# Yun_Shield_Teensy_Adapter.net
KiCad netlist of a schematic drawn in EAGLE
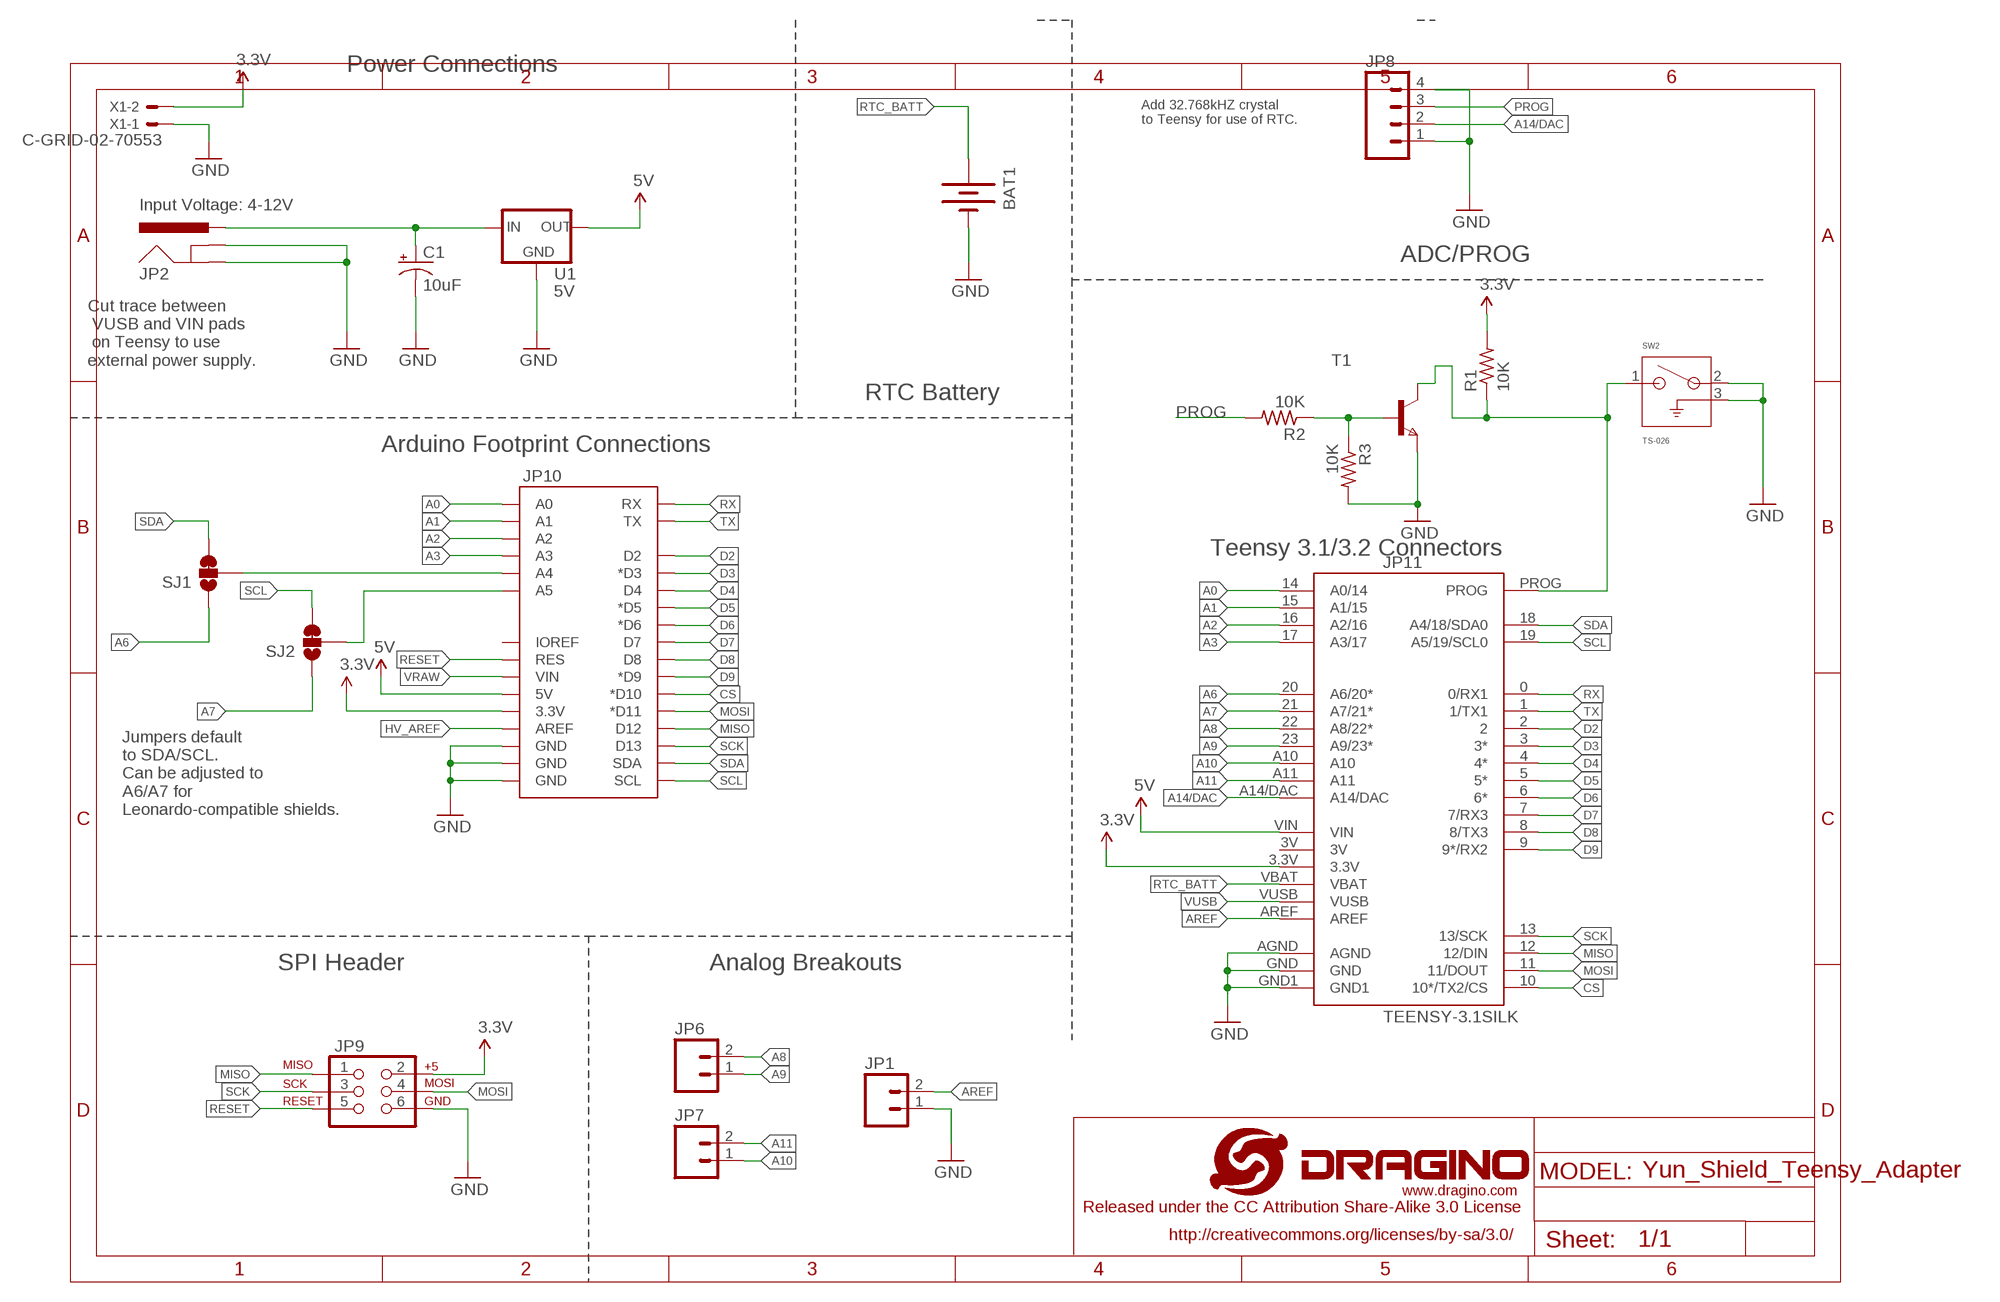
[diagram p0: schematic, sheet 1]

(export (version "E")
  (design (tool "Eeschema 10.0.6"))
  (components
    (comp (ref "BAT1")
      (value "BATTERY12PTH")
      (footprint "eagle-import:BATTCON_12MM_PTH")
      (libsource (lib "eagle-import") (part "BATTERY12PTH"))
    )
    (comp (ref "C1")
      (value "10uF")
      (footprint "eagle-import:CPOL-RADIAL-10UF-25V")
      (libsource (lib "eagle-import") (part "10UF-25V-20%(PTH)"))
    )
    (comp (ref "JP1")
      (value "M02PTH")
      (footprint "eagle-import:1X02")
      (libsource (lib "eagle-import") (part "M02PTH"))
    )
    (comp (ref "JP2")
      (value "POWER_JACKPTH_LOCK")
      (footprint "eagle-import:POWER_JACK_PTH_LOCK")
      (libsource (lib "eagle-import") (part "POWER_JACKPTH_LOCK"))
    )
    (comp (ref "JP6")
      (value "M02PTH")
      (footprint "eagle-import:1X02")
      (libsource (lib "eagle-import") (part "M02PTH"))
    )
    (comp (ref "JP7")
      (value "M02PTH")
      (footprint "eagle-import:1X02")
      (libsource (lib "eagle-import") (part "M02PTH"))
    )
    (comp (ref "JP8")
      (value "M04PTH")
      (footprint "eagle-import:1X04")
      (libsource (lib "eagle-import") (part "M04PTH"))
    )
    (comp (ref "JP9")
      (value "AVR_SPI_PRG_6PTH")
      (footprint "eagle-import:2X3")
      (libsource (lib "eagle-import") (part "AVR_SPI_PRG_6PTH"))
    )
    (comp (ref "JP10")
      (value "ARDUINO_R3_SHIELDUNO_R3_SHIELD_HOLES")
      (footprint "eagle-import:UNO_R3_SHIELD_HOLES")
      (libsource (lib "eagle-import") (part "ARDUINO_R3_SHIELDUNO_R3_SHIELD_HOLES"))
    )
    (comp (ref "JP11")
      (value "TEENSY-3.1SILK")
      (footprint "eagle-import:TEENSY-3.1")
      (libsource (lib "eagle-import") (part "TEENSY-3.1SILK"))
    )
    (comp (ref "R1")
      (value "10K")
      (footprint "eagle-import:0204_5")
      (libsource (lib "eagle-import") (part "R-US_0204/5"))
    )
    (comp (ref "R2")
      (value "10K")
      (footprint "eagle-import:0204_5")
      (libsource (lib "eagle-import") (part "R-US_0204/5"))
    )
    (comp (ref "R3")
      (value "10K")
      (footprint "eagle-import:0204_5")
      (libsource (lib "eagle-import") (part "R-US_0204/5"))
    )
    (comp (ref "SJ1")
      (value "JUMPER-PAD-3-2OF3_NC_BY_TRACE_SMALL")
      (footprint "eagle-import:PAD-JUMPER-3-2OF3_NC_BY_TRACE_YES_SILK_FULL_BOX")
      (libsource (lib "eagle-import") (part "JUMPER-PAD-3-2OF3_NC_BY_TRACE_SMALL"))
    )
    (comp (ref "SJ2")
      (value "JUMPER-PAD-3-2OF3_NC_BY_TRACE_SMALL")
      (footprint "eagle-import:PAD-JUMPER-3-2OF3_NC_BY_TRACE_YES_SILK_FULL_BOX")
      (libsource (lib "eagle-import") (part "JUMPER-PAD-3-2OF3_NC_BY_TRACE_SMALL"))
    )
    (comp (ref "SW2")
      (value "TS-026")
      (footprint "eagle-import:TS-026")
      (libsource (lib "eagle-import") (part "TS-026"))
    )
    (comp (ref "T1")
      (value "NPN-E3L")
      (footprint "eagle-import:E3LINE")
      (libsource (lib "eagle-import") (part "NPN-E3L"))
    )
    (comp (ref "U$1")
      (value "LOGO-NEW")
      (footprint "eagle-import:LOGO-SILK-NEW")
      (libsource (lib "eagle-import") (part "LOGO-NEW"))
    )
    (comp (ref "U1")
      (value "5V")
      (footprint "eagle-import:TO-220-ALT")
      (libsource (lib "eagle-import") (part "V_REG_78XX-TO-220"))
    )
    (comp (ref "X1")
      (value "C-GRID-02-70553")
      (footprint "eagle-import:70553-02")
      (libsource (lib "eagle-import") (part "C-GRID-02-70553"))
    )
  )
  (nets
    (net (code "1") (name "3.3V") (class "Default")
      (node (ref "JP10") (pin "3.3V") (pinfunction "3.3V_3.3V") (pintype "bidirectional"))
      (node (ref "JP11") (pin "3.3V") (pinfunction "3.3V_3.3V") (pintype "bidirectional"))
      (node (ref "JP9") (pin "2") (pinfunction "2_2") (pintype "passive"))
      (node (ref "R1") (pin "2") (pinfunction "2_2") (pintype "passive"))
      (node (ref "X1") (pin "2") (pinfunction "S_2") (pintype "passive"))
    )
    (net (code "2") (name "5V") (class "Default")
      (node (ref "JP10") (pin "5V") (pinfunction "5V_5V") (pintype "bidirectional"))
      (node (ref "JP11") (pin "VIN") (pinfunction "VIN_VIN") (pintype "bidirectional"))
      (node (ref "U1") (pin "OUT") (pinfunction "OUT_OUT") (pintype "output"))
    )
    (net (code "3") (name "A0") (class "Default")
      (node (ref "JP10") (pin "A0") (pinfunction "A0_A0") (pintype "bidirectional"))
      (node (ref "JP11") (pin "14") (pinfunction "A0/14_14") (pintype "bidirectional"))
    )
    (net (code "4") (name "A1") (class "Default")
      (node (ref "JP10") (pin "A1") (pinfunction "A1_A1") (pintype "bidirectional"))
      (node (ref "JP11") (pin "15") (pinfunction "A1/15_15") (pintype "bidirectional"))
    )
    (net (code "5") (name "A2") (class "Default")
      (node (ref "JP10") (pin "A2") (pinfunction "A2_A2") (pintype "bidirectional"))
      (node (ref "JP11") (pin "16") (pinfunction "A2/16_16") (pintype "bidirectional"))
    )
    (net (code "6") (name "A3") (class "Default")
      (node (ref "JP10") (pin "A3") (pinfunction "A3_A3") (pintype "bidirectional"))
      (node (ref "JP11") (pin "17") (pinfunction "A3/17_17") (pintype "bidirectional"))
    )
    (net (code "7") (name "A6") (class "Default")
      (node (ref "JP11") (pin "20") (pinfunction "A6/20*_20") (pintype "bidirectional"))
      (node (ref "SJ1") (pin "1") (pinfunction "1_1") (pintype "passive"))
    )
    (net (code "8") (name "A7") (class "Default")
      (node (ref "JP11") (pin "21") (pinfunction "A7/21*_21") (pintype "bidirectional"))
      (node (ref "SJ2") (pin "1") (pinfunction "1_1") (pintype "passive"))
    )
    (net (code "9") (name "A8") (class "Default")
      (node (ref "JP11") (pin "22") (pinfunction "A8/22*_22") (pintype "bidirectional"))
      (node (ref "JP6") (pin "2") (pinfunction "2_2") (pintype "passive"))
    )
    (net (code "10") (name "A9") (class "Default")
      (node (ref "JP11") (pin "23") (pinfunction "A9/23*_23") (pintype "bidirectional"))
      (node (ref "JP6") (pin "1") (pinfunction "1_1") (pintype "passive"))
    )
    (net (code "11") (name "A10") (class "Default")
      (node (ref "JP11") (pin "A10") (pinfunction "A10_A10") (pintype "bidirectional"))
      (node (ref "JP7") (pin "1") (pinfunction "1_1") (pintype "passive"))
    )
    (net (code "12") (name "A11") (class "Default")
      (node (ref "JP11") (pin "A11") (pinfunction "A11_A11") (pintype "bidirectional"))
      (node (ref "JP7") (pin "2") (pinfunction "2_2") (pintype "passive"))
    )
    (net (code "13") (name "A14{slash}DAC") (class "Default")
      (node (ref "JP11") (pin "A14/DAC") (pinfunction "A14/DAC_A14/DAC") (pintype "bidirectional"))
      (node (ref "JP8") (pin "2") (pinfunction "2_2") (pintype "passive"))
    )
    (net (code "14") (name "AREF") (class "Default")
      (node (ref "JP1") (pin "2") (pinfunction "2_2") (pintype "passive"))
      (node (ref "JP11") (pin "AREF") (pinfunction "AREF_AREF") (pintype "bidirectional"))
    )
    (net (code "15") (name "CS") (class "Default")
      (node (ref "JP10") (pin "D10") (pinfunction "*D10_D10") (pintype "bidirectional"))
      (node (ref "JP11") (pin "10") (pinfunction "10*/TX2/CS_10") (pintype "bidirectional"))
    )
    (net (code "16") (name "D2") (class "Default")
      (node (ref "JP10") (pin "D2") (pinfunction "D2_D2") (pintype "bidirectional"))
      (node (ref "JP11") (pin "2") (pinfunction "2_2") (pintype "bidirectional"))
    )
    (net (code "17") (name "D3") (class "Default")
      (node (ref "JP10") (pin "D3") (pinfunction "*D3_D3") (pintype "bidirectional"))
      (node (ref "JP11") (pin "3") (pinfunction "3*_3") (pintype "bidirectional"))
    )
    (net (code "18") (name "D4") (class "Default")
      (node (ref "JP10") (pin "D4") (pinfunction "D4_D4") (pintype "bidirectional"))
      (node (ref "JP11") (pin "4") (pinfunction "4*_4") (pintype "bidirectional"))
    )
    (net (code "19") (name "D5") (class "Default")
      (node (ref "JP10") (pin "D5") (pinfunction "*D5_D5") (pintype "bidirectional"))
      (node (ref "JP11") (pin "5") (pinfunction "5*_5") (pintype "bidirectional"))
    )
    (net (code "20") (name "D6") (class "Default")
      (node (ref "JP10") (pin "D6") (pinfunction "*D6_D6") (pintype "bidirectional"))
      (node (ref "JP11") (pin "6") (pinfunction "6*_6") (pintype "bidirectional"))
    )
    (net (code "21") (name "D7") (class "Default")
      (node (ref "JP10") (pin "D7") (pinfunction "D7_D7") (pintype "bidirectional"))
      (node (ref "JP11") (pin "7") (pinfunction "7/RX3_7") (pintype "bidirectional"))
    )
    (net (code "22") (name "D8") (class "Default")
      (node (ref "JP10") (pin "D8") (pinfunction "D8_D8") (pintype "bidirectional"))
      (node (ref "JP11") (pin "8") (pinfunction "8/TX3_8") (pintype "bidirectional"))
    )
    (net (code "23") (name "D9") (class "Default")
      (node (ref "JP10") (pin "D9") (pinfunction "*D9_D9") (pintype "bidirectional"))
      (node (ref "JP11") (pin "9") (pinfunction "9*/RX2_9") (pintype "bidirectional"))
    )
    (net (code "24") (name "GND") (class "Default")
      (node (ref "BAT1") (pin "GND") (pinfunction "-_GND") (pintype "power_in"))
      (node (ref "C1") (pin "2") (pinfunction "-_2") (pintype "passive"))
      (node (ref "JP1") (pin "1") (pinfunction "1_1") (pintype "passive"))
      (node (ref "JP10") (pin "GND@0") (pinfunction "GND_GND@0") (pintype "bidirectional"))
      (node (ref "JP10") (pin "GND@1") (pinfunction "GND_GND@1") (pintype "bidirectional"))
      (node (ref "JP10") (pin "GND@2") (pinfunction "GND_GND@2") (pintype "bidirectional"))
      (node (ref "JP11") (pin "AGND") (pinfunction "AGND_AGND") (pintype "bidirectional"))
      (node (ref "JP11") (pin "GND") (pinfunction "GND_GND") (pintype "bidirectional"))
      (node (ref "JP11") (pin "GND1") (pinfunction "GND1_GND1") (pintype "bidirectional"))
      (node (ref "JP2") (pin "GND") (pinfunction "GND_GND") (pintype "bidirectional"))
      (node (ref "JP2") (pin "GNDBREAK") (pinfunction "GNDBREAK_GNDBREAK") (pintype "bidirectional"))
      (node (ref "JP8") (pin "1") (pinfunction "1_1") (pintype "passive"))
      (node (ref "JP8") (pin "4") (pinfunction "4_4") (pintype "passive"))
      (node (ref "JP9") (pin "6") (pinfunction "6_6") (pintype "passive"))
      (node (ref "R3") (pin "2") (pinfunction "2_2") (pintype "passive"))
      (node (ref "SW2") (pin "2") (pinfunction "2_2") (pintype "bidirectional"))
      (node (ref "SW2") (pin "3") (pinfunction "3_3") (pintype "bidirectional"))
      (node (ref "T1") (pin "3") (pinfunction "E_3") (pintype "passive"))
      (node (ref "U1") (pin "GND") (pinfunction "GND_GND") (pintype "input"))
      (node (ref "X1") (pin "1") (pinfunction "S_1") (pintype "passive"))
    )
    (net (code "25") (name "HV_AREF") (class "Default")
      (node (ref "JP10") (pin "AREF") (pinfunction "AREF_AREF") (pintype "bidirectional"))
    )
    (net (code "26") (name "MISO") (class "Default")
      (node (ref "JP10") (pin "D12") (pinfunction "D12_D12") (pintype "bidirectional"))
      (node (ref "JP11") (pin "12") (pinfunction "12/DIN_12") (pintype "bidirectional"))
      (node (ref "JP9") (pin "1") (pinfunction "1_1") (pintype "passive"))
    )
    (net (code "27") (name "MOSI") (class "Default")
      (node (ref "JP10") (pin "D11") (pinfunction "*D11_D11") (pintype "bidirectional"))
      (node (ref "JP11") (pin "11") (pinfunction "11/DOUT_11") (pintype "bidirectional"))
      (node (ref "JP9") (pin "4") (pinfunction "4_4") (pintype "passive"))
    )
    (net (code "28") (name "Net-(JP10-PadA4)") (class "Default")
      (node (ref "JP10") (pin "A4") (pinfunction "A4_A4") (pintype "bidirectional"))
      (node (ref "SJ1") (pin "2") (pinfunction "2_2") (pintype "passive"))
    )
    (net (code "29") (name "Net-(JP10-PadA5)") (class "Default")
      (node (ref "JP10") (pin "A5") (pinfunction "A5_A5") (pintype "bidirectional"))
      (node (ref "SJ2") (pin "2") (pinfunction "2_2") (pintype "passive"))
    )
    (net (code "30") (name "Net-(T1-B)") (class "Default")
      (node (ref "R2") (pin "1") (pinfunction "1_1") (pintype "passive"))
      (node (ref "R3") (pin "1") (pinfunction "1_1") (pintype "passive"))
      (node (ref "T1") (pin "2") (pinfunction "B_2") (pintype "passive"))
    )
    (net (code "31") (name "Net-(T1-C)") (class "Default")
      (node (ref "JP11") (pin "PROG") (pinfunction "PROG_PROG") (pintype "bidirectional"))
      (node (ref "R1") (pin "1") (pinfunction "1_1") (pintype "passive"))
      (node (ref "SW2") (pin "1") (pinfunction "1_1") (pintype "bidirectional"))
      (node (ref "T1") (pin "1") (pinfunction "C_1") (pintype "passive"))
    )
    (net (code "32") (name "PROG") (class "Default")
      (node (ref "JP8") (pin "3") (pinfunction "3_3") (pintype "passive"))
      (node (ref "R2") (pin "2") (pinfunction "2_2") (pintype "passive"))
    )
    (net (code "33") (name "RESET") (class "Default")
      (node (ref "JP10") (pin "RES") (pinfunction "RES_RES") (pintype "bidirectional"))
      (node (ref "JP9") (pin "5") (pinfunction "5_5") (pintype "passive"))
    )
    (net (code "34") (name "RTC_BATT") (class "Default")
      (node (ref "BAT1") (pin "VCC@1") (pinfunction "+_VCC@1") (pintype "power_in"))
      (node (ref "JP11") (pin "VBAT") (pinfunction "VBAT_VBAT") (pintype "bidirectional"))
    )
    (net (code "35") (name "RX") (class "Default")
      (node (ref "JP10") (pin "RX") (pinfunction "RX_RX") (pintype "bidirectional"))
      (node (ref "JP11") (pin "0") (pinfunction "0/RX1_0") (pintype "bidirectional"))
    )
    (net (code "36") (name "SCK") (class "Default")
      (node (ref "JP10") (pin "D13") (pinfunction "D13_D13") (pintype "bidirectional"))
      (node (ref "JP11") (pin "13") (pinfunction "13/SCK_13") (pintype "bidirectional"))
      (node (ref "JP9") (pin "3") (pinfunction "3_3") (pintype "passive"))
    )
    (net (code "37") (name "SCL") (class "Default")
      (node (ref "JP10") (pin "SCL") (pinfunction "SCL_SCL") (pintype "bidirectional"))
      (node (ref "JP11") (pin "19") (pinfunction "A5/19/SCL0_19") (pintype "bidirectional"))
      (node (ref "SJ2") (pin "3") (pinfunction "3_3") (pintype "passive"))
    )
    (net (code "38") (name "SDA") (class "Default")
      (node (ref "JP10") (pin "SDA") (pinfunction "SDA_SDA") (pintype "bidirectional"))
      (node (ref "JP11") (pin "18") (pinfunction "A4/18/SDA0_18") (pintype "bidirectional"))
      (node (ref "SJ1") (pin "3") (pinfunction "3_3") (pintype "passive"))
    )
    (net (code "39") (name "TX") (class "Default")
      (node (ref "JP10") (pin "TX") (pinfunction "TX_TX") (pintype "bidirectional"))
      (node (ref "JP11") (pin "1") (pinfunction "1/TX1_1") (pintype "bidirectional"))
    )
    (net (code "40") (name "VRAW") (class "Default")
      (node (ref "C1") (pin "1") (pinfunction "+_1") (pintype "passive"))
      (node (ref "JP10") (pin "VIN") (pinfunction "VIN_VIN") (pintype "bidirectional"))
      (node (ref "JP2") (pin "PWR") (pinfunction "PWR_PWR") (pintype "bidirectional"))
      (node (ref "U1") (pin "IN") (pinfunction "IN_IN") (pintype "input"))
    )
    (net (code "41") (name "VUSB") (class "Default")
      (node (ref "JP11") (pin "VUSB") (pinfunction "VUSB_VUSB") (pintype "bidirectional"))
    )
    (net (code "42") (name "unconnected-(JP10-PadIOREF)") (class "Default")
      (node (ref "JP10") (pin "IOREF") (pinfunction "IOREF_IOREF") (pintype "bidirectional"))
    )
    (net (code "43") (name "unconnected-(JP11-Pad3V)") (class "Default")
      (node (ref "JP11") (pin "3V") (pinfunction "3V_3V") (pintype "bidirectional"))
    )
  )
)
